# loadCell_Amplifier_v2_0.net
KiCad netlist of a schematic drawn in EAGLE
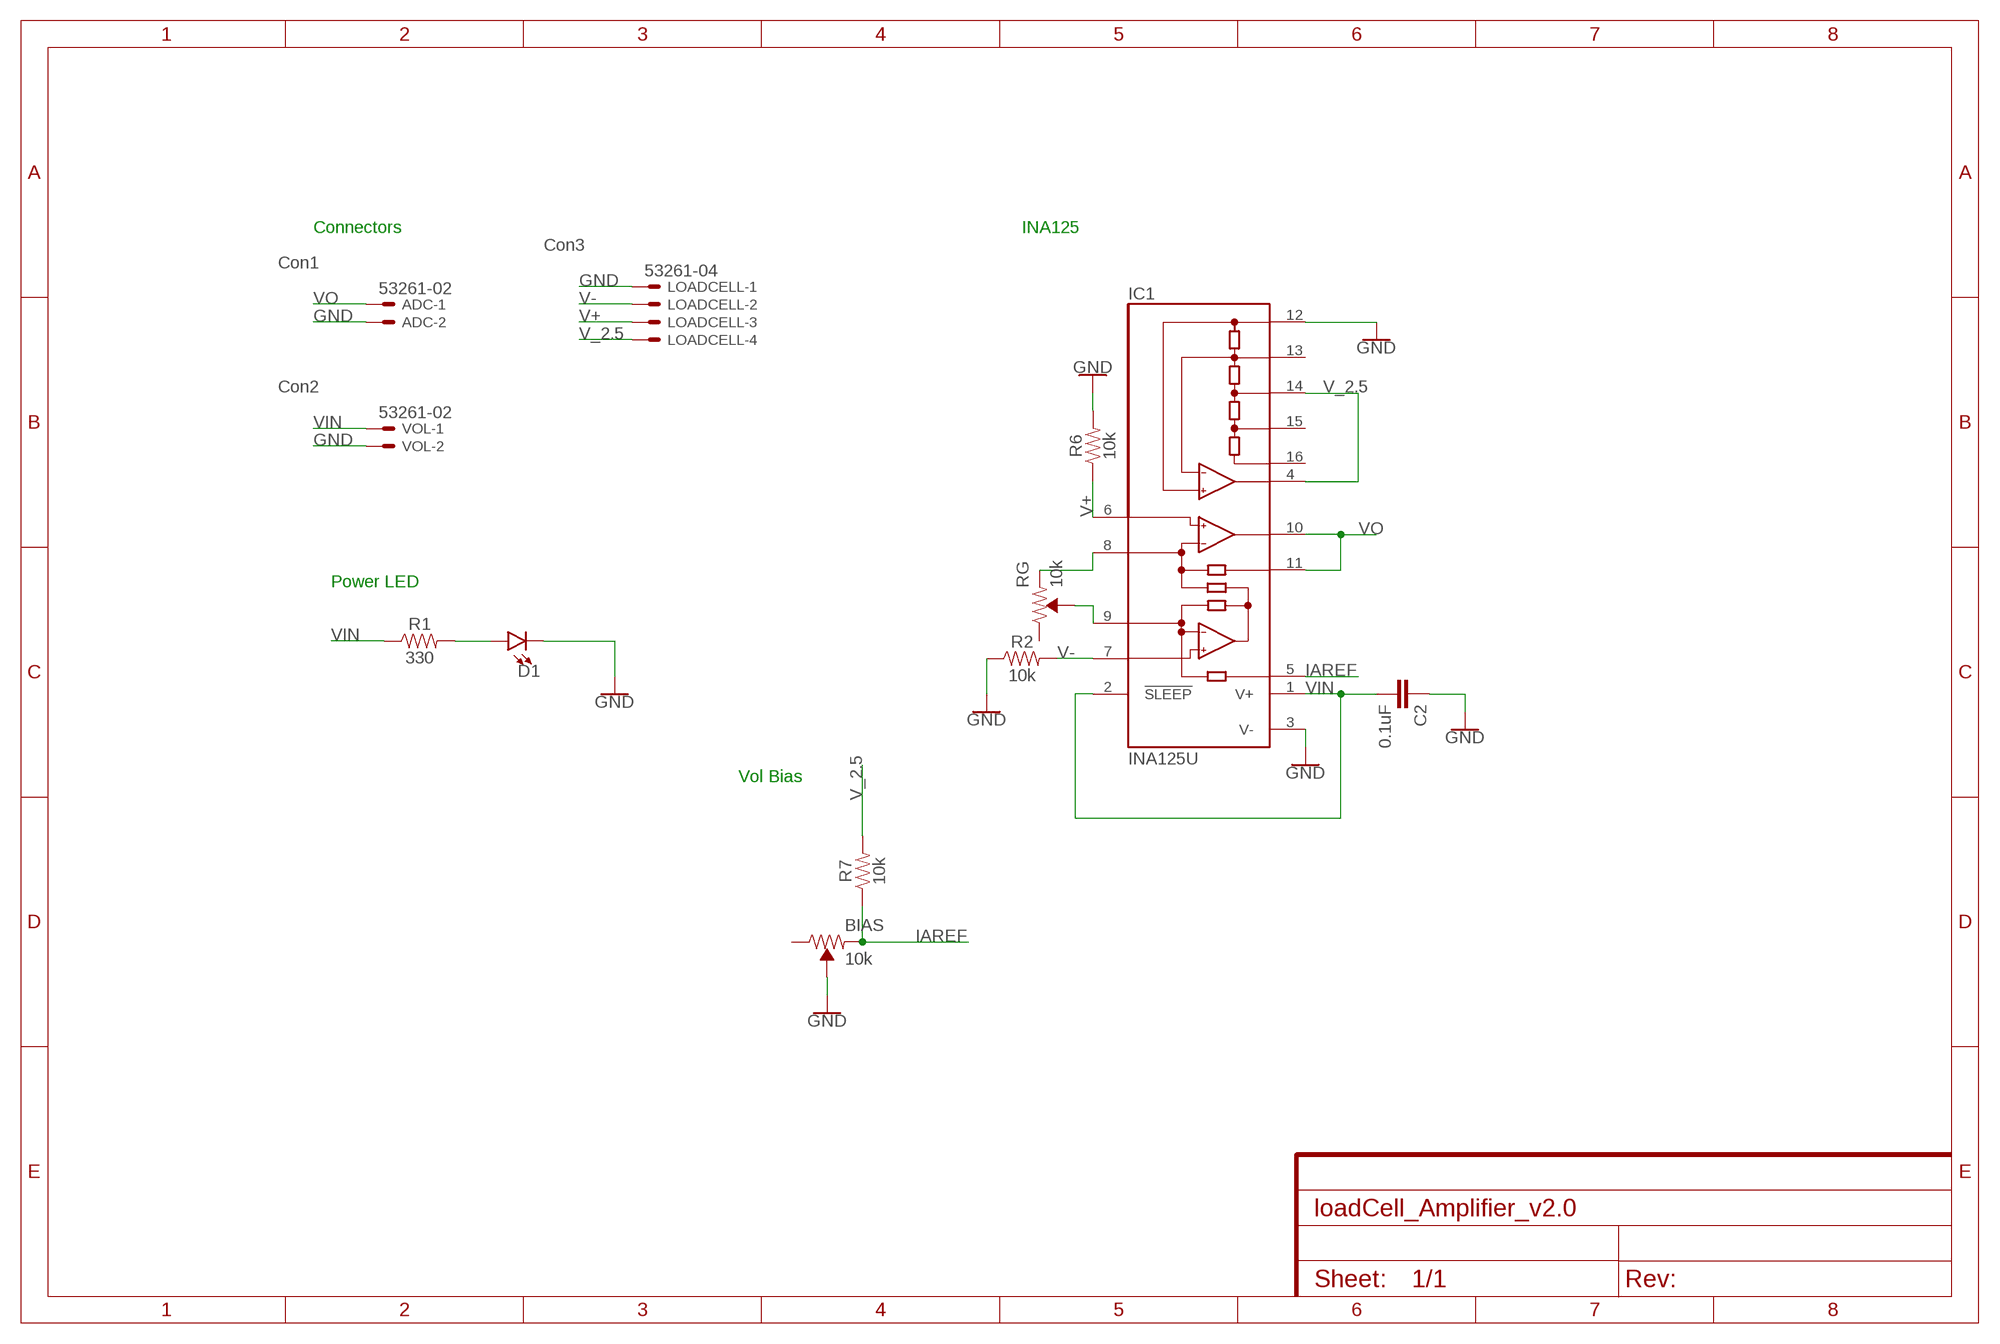
[diagram p0: schematic, sheet 1]

(export (version "E")
  (design (tool "Eeschema 10.0.6"))
  (components
    (comp (ref "ADC")
      (value "53261-02")
      (footprint "eagle-import:53261-02")
      (libsource (lib "eagle-import") (part "53?-02261"))
    )
    (comp (ref "BIAS")
      (value "10k")
      (footprint "eagle-import:TRIMPOT-PTH-3386U")
      (libsource (lib "eagle-import") (part "TRIMPOT-PTH-10MM-KNOB-1/2W-10%"))
    )
    (comp (ref "C2")
      (value "0.1uF")
      (footprint "eagle-import:CAP-PTH-SMALL-KIT")
      (libsource (lib "eagle-import") (part "0.1UF-KIT-EZ-50V-20%"))
    )
    (comp (ref "D1")
      (value "LED0603")
      (footprint "eagle-import:LED-0603")
      (libsource (lib "eagle-import") (part "LED0603"))
    )
    (comp (ref "IC1")
      (value "INA125U")
      (footprint "eagle-import:SO16-1")
      (fields (field (name "MF") "TEXAS INSTRUMENT CONNECTORS"))
      (libsource (lib "eagle-import") (part "INA125U"))
    )
    (comp (ref "LOADCELL")
      (value "53261-04")
      (footprint "eagle-import:53261-04")
      (libsource (lib "eagle-import") (part "53?-04261"))
    )
    (comp (ref "R1")
      (value "330")
      (footprint "eagle-import:0603")
      (libsource (lib "eagle-import") (part "0.05OHM-0603-1/5W-1%"))
    )
    (comp (ref "R2")
      (value "10k")
      (footprint "eagle-import:0603")
      (libsource (lib "eagle-import") (part "0.05OHM-0603-1/5W-1%"))
    )
    (comp (ref "R6")
      (value "10k")
      (footprint "eagle-import:0603")
      (libsource (lib "eagle-import") (part "0.05OHM-0603-1/5W-1%"))
    )
    (comp (ref "R7")
      (value "10k")
      (footprint "eagle-import:0603")
      (libsource (lib "eagle-import") (part "0.05OHM-0603-1/5W-1%"))
    )
    (comp (ref "RG")
      (value "10k")
      (footprint "eagle-import:TRIMPOT-PTH-3386U")
      (libsource (lib "eagle-import") (part "TRIMPOT-PTH-10MM-KNOB-1/2W-10%"))
    )
    (comp (ref "VOL")
      (value "53261-02")
      (footprint "eagle-import:53261-02")
      (libsource (lib "eagle-import") (part "53?-02261"))
    )
  )
  (nets
    (net (code "1") (name "/IAREF") (class "Default")
      (node (ref "BIAS") (pin "1") (pinfunction "CCW_1") (pintype "passive"))
      (node (ref "IC1") (pin "5") (pinfunction "REF_5") (pintype "passive"))
      (node (ref "R7") (pin "1") (pinfunction "1_1") (pintype "passive"))
    )
    (net (code "2") (name "/V+") (class "Default")
      (node (ref "IC1") (pin "6") (pinfunction "+IN_6") (pintype "input"))
      (node (ref "LOADCELL") (pin "3") (pinfunction "S_3") (pintype "passive"))
      (node (ref "R6") (pin "1") (pinfunction "1_1") (pintype "passive"))
    )
    (net (code "3") (name "/V-") (class "Default")
      (node (ref "IC1") (pin "7") (pinfunction "-IN_7") (pintype "input"))
      (node (ref "LOADCELL") (pin "2") (pinfunction "S_2") (pintype "passive"))
      (node (ref "R2") (pin "2") (pinfunction "2_2") (pintype "passive"))
    )
    (net (code "4") (name "/VIN") (class "Default")
      (node (ref "C2") (pin "2") (pinfunction "2_2") (pintype "passive"))
      (node (ref "IC1") (pin "1") (pinfunction "V+_1") (pintype "power_in"))
      (node (ref "IC1") (pin "2") (pinfunction "~{SLEEP}_2") (pintype "input"))
      (node (ref "R1") (pin "1") (pinfunction "1_1") (pintype "passive"))
      (node (ref "VOL") (pin "1") (pinfunction "S_1") (pintype "passive"))
    )
    (net (code "5") (name "/VO") (class "Default")
      (node (ref "ADC") (pin "1") (pinfunction "S_1") (pintype "passive"))
      (node (ref "IC1") (pin "10") (pinfunction "OUT_10") (pintype "output"))
      (node (ref "IC1") (pin "11") (pinfunction "SENSE_11") (pintype "passive"))
    )
    (net (code "6") (name "/V_2.5") (class "Default")
      (node (ref "IC1") (pin "14") (pinfunction "REF2.5_14") (pintype "output"))
      (node (ref "IC1") (pin "4") (pinfunction "REFOUT_4") (pintype "output"))
      (node (ref "LOADCELL") (pin "4") (pinfunction "S_4") (pintype "passive"))
      (node (ref "R7") (pin "2") (pinfunction "2_2") (pintype "passive"))
    )
    (net (code "7") (name "GND") (class "Default")
      (node (ref "ADC") (pin "2") (pinfunction "S_2") (pintype "passive"))
      (node (ref "BIAS") (pin "2") (pinfunction "WIPER_2") (pintype "passive"))
      (node (ref "C2") (pin "1") (pinfunction "1_1") (pintype "passive"))
      (node (ref "D1") (pin "C") (pinfunction "C_C") (pintype "passive"))
      (node (ref "IC1") (pin "12") (pinfunction "REFCOM_12") (pintype "passive"))
      (node (ref "IC1") (pin "3") (pinfunction "V-_3") (pintype "power_in"))
      (node (ref "LOADCELL") (pin "1") (pinfunction "S_1") (pintype "passive"))
      (node (ref "R2") (pin "1") (pinfunction "1_1") (pintype "passive"))
      (node (ref "R6") (pin "2") (pinfunction "2_2") (pintype "passive"))
      (node (ref "VOL") (pin "2") (pinfunction "S_2") (pintype "passive"))
    )
    (net (code "8") (name "Net-(D1-PadA)") (class "Default")
      (node (ref "D1") (pin "A") (pinfunction "A_A") (pintype "passive"))
      (node (ref "R1") (pin "2") (pinfunction "2_2") (pintype "passive"))
    )
    (net (code "9") (name "Net-(RG-CCW)") (class "Default")
      (node (ref "IC1") (pin "8") (pinfunction "RG_8") (pintype "passive"))
      (node (ref "RG") (pin "1") (pinfunction "CCW_1") (pintype "passive"))
    )
    (net (code "10") (name "Net-(RG-WIPER)") (class "Default")
      (node (ref "IC1") (pin "9") (pinfunction "RG_9") (pintype "passive"))
      (node (ref "RG") (pin "2") (pinfunction "WIPER_2") (pintype "passive"))
    )
    (net (code "11") (name "unconnected-(BIAS-CW-Pad3)") (class "Default")
      (node (ref "BIAS") (pin "3") (pinfunction "CW_3") (pintype "passive"))
    )
    (net (code "12") (name "unconnected-(IC1-REF5-Pad15)") (class "Default")
      (node (ref "IC1") (pin "15") (pinfunction "REF5_15") (pintype "output"))
    )
    (net (code "13") (name "unconnected-(IC1-REF10-Pad16)") (class "Default")
      (node (ref "IC1") (pin "16") (pinfunction "REF10_16") (pintype "output"))
    )
    (net (code "14") (name "unconnected-(IC1-REFBG-Pad13)") (class "Default")
      (node (ref "IC1") (pin "13") (pinfunction "REFBG_13") (pintype "output"))
    )
    (net (code "15") (name "unconnected-(RG-CW-Pad3)") (class "Default")
      (node (ref "RG") (pin "3") (pinfunction "CW_3") (pintype "passive"))
    )
  )
)
